# SmartGarden.net
KiCad netlist of a schematic drawn in Altium Designer
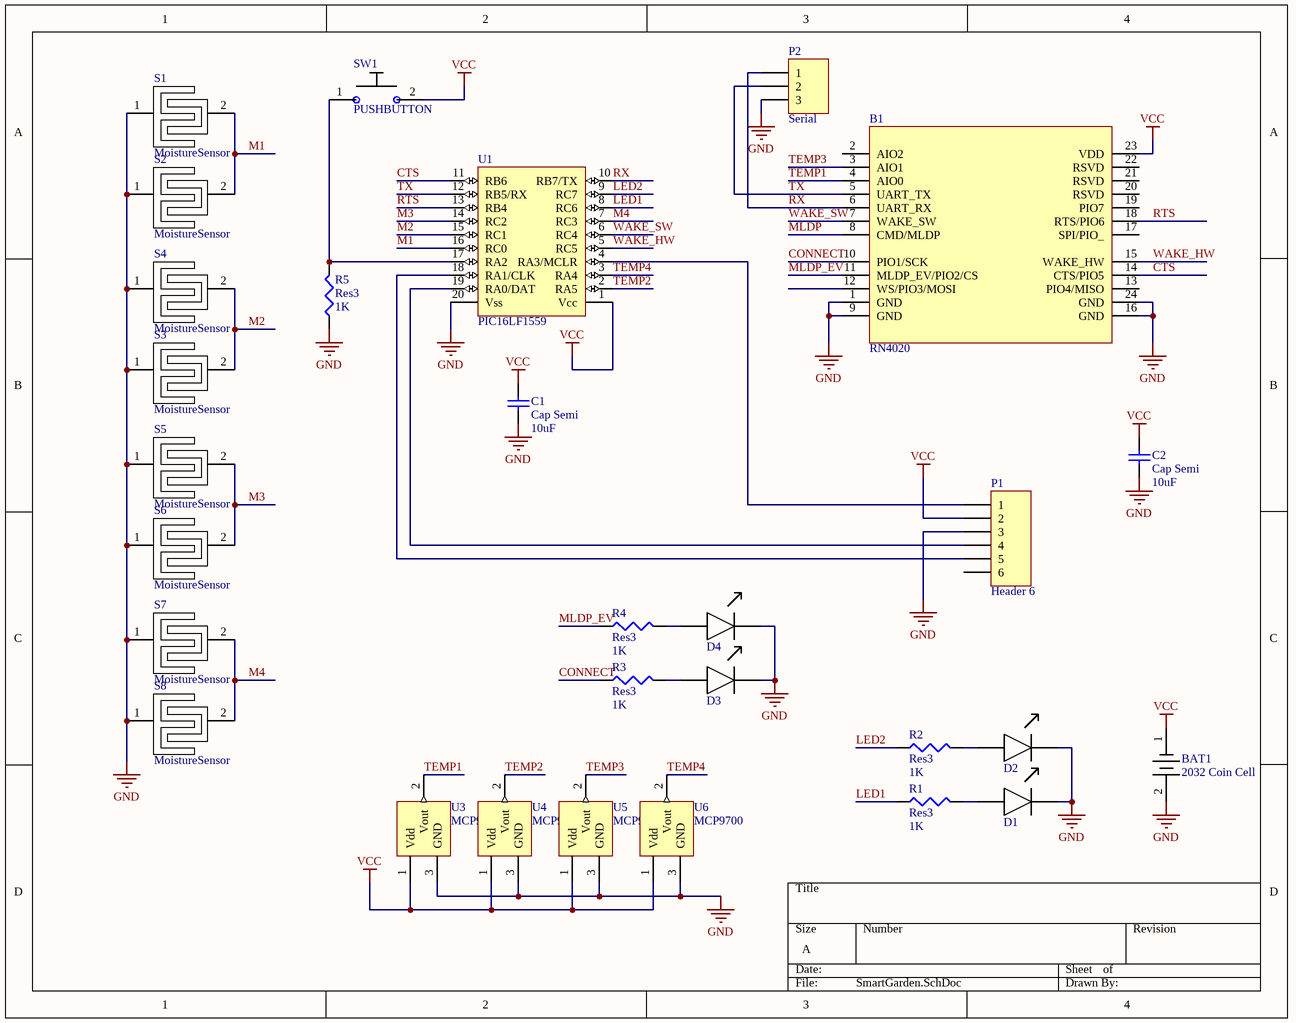
[diagram p0: SmartGarden.SchDoc]

(export (version "E")
  (design (tool "Eeschema 10.0.6"))
  (components
    (comp (ref "B1") (value "RN4020") (footprint "RN4020 MODULE-24") (libsource (lib "Phil") (part "RN4020")))
    (comp (ref "BAT1")
      (value "2032 Coin Cell")
      (footprint "1063TR-CoinCell")
      (libsource (lib "Phil") (part "2032 Coin Cell"))
    )
    (comp (ref "C1")
      (value "Cap Semi")
      (footprint "1608[0603]")
      (description "Capacitor (Semiconductor SIM Model)")
      (fields (field (name "ALTIUM_VALUE") "10uF") (field (name "PUBLISHER") "Altium Limited"))
      (libsource (lib "Miscellaneous Devices") (part "Cap Semi"))
    )
    (comp (ref "C2")
      (value "Cap Semi")
      (footprint "1608[0603]")
      (description "Capacitor (Semiconductor SIM Model)")
      (fields (field (name "ALTIUM_VALUE") "10uF") (field (name "PUBLISHER") "Altium Limited"))
      (libsource (lib "Miscellaneous Devices") (part "Cap Semi"))
    )
    (comp (ref "D1") (value "LED") (footprint "603_") (libsource (lib "Phil") (part "LED")))
    (comp (ref "D2") (value "LED") (footprint "603_") (libsource (lib "Phil") (part "LED")))
    (comp (ref "D3") (value "LED") (footprint "603_") (libsource (lib "Phil") (part "LED")))
    (comp (ref "D4") (value "LED") (footprint "603_") (libsource (lib "Phil") (part "LED")))
    (comp (ref "P1")
      (value "Header 6")
      (footprint "HDR1X6")
      (description "Header, 6-Pin")
      (fields (field (name "PUBLISHER") "Altium Limited"))
      (libsource (lib "Miscellaneous Connectors") (part "Header 6"))
    )
    (comp (ref "P2")
      (value "Serial")
      (footprint "HDR1X3")
      (description "Header, 3-Pin")
      (fields (field (name "PUBLISHER") "Altium Limited"))
      (libsource (lib "Miscellaneous Connectors") (part "Header 3"))
    )
    (comp (ref "R1")
      (value "Res3")
      (footprint "J1-0603")
      (description "Resistor")
      (fields (field (name "ALTIUM_VALUE") "1K") (field (name "PUBLISHER") "Altium Limited"))
      (libsource (lib "Miscellaneous Devices") (part "Res3"))
    )
    (comp (ref "R2")
      (value "Res3")
      (footprint "J1-0603")
      (description "Resistor")
      (fields (field (name "ALTIUM_VALUE") "1K") (field (name "PUBLISHER") "Altium Limited"))
      (libsource (lib "Miscellaneous Devices") (part "Res3"))
    )
    (comp (ref "R3")
      (value "Res3")
      (footprint "J1-0603")
      (description "Resistor")
      (fields (field (name "ALTIUM_VALUE") "1K") (field (name "PUBLISHER") "Altium Limited"))
      (libsource (lib "Miscellaneous Devices") (part "Res3"))
    )
    (comp (ref "R4")
      (value "Res3")
      (footprint "J1-0603")
      (description "Resistor")
      (fields (field (name "ALTIUM_VALUE") "1K") (field (name "PUBLISHER") "Altium Limited"))
      (libsource (lib "Miscellaneous Devices") (part "Res3"))
    )
    (comp (ref "R5")
      (value "Res3")
      (footprint "J1-0603")
      (description "Resistor")
      (fields (field (name "ALTIUM_VALUE") "1K") (field (name "PUBLISHER") "Altium Limited"))
      (libsource (lib "Miscellaneous Devices") (part "Res3"))
    )
    (comp (ref "S1")
      (value "MoistureSensor")
      (footprint "MOISTURE_2")
      (libsource (lib "Phil") (part "MoistureSensor"))
    )
    (comp (ref "S2")
      (value "MoistureSensor")
      (footprint "MOISTURE_2")
      (libsource (lib "Phil") (part "MoistureSensor"))
    )
    (comp (ref "S3")
      (value "MoistureSensor")
      (footprint "MOISTURE_2")
      (libsource (lib "Phil") (part "MoistureSensor"))
    )
    (comp (ref "S4")
      (value "MoistureSensor")
      (footprint "MOISTURE_2")
      (libsource (lib "Phil") (part "MoistureSensor"))
    )
    (comp (ref "S5")
      (value "MoistureSensor")
      (footprint "MOISTURE_2")
      (libsource (lib "Phil") (part "MoistureSensor"))
    )
    (comp (ref "S6")
      (value "MoistureSensor")
      (footprint "MOISTURE_2")
      (libsource (lib "Phil") (part "MoistureSensor"))
    )
    (comp (ref "S7")
      (value "MoistureSensor")
      (footprint "MOISTURE_2")
      (libsource (lib "Phil") (part "MoistureSensor"))
    )
    (comp (ref "S8")
      (value "MoistureSensor")
      (footprint "MOISTURE_2")
      (libsource (lib "Phil") (part "MoistureSensor"))
    )
    (comp (ref "SW1")
      (value "PUSHBUTTON")
      (footprint "PUSHBUTTON")
      (description "TE 5-1437565-0")
      (libsource (lib "Phil") (part "PUSHBUTTON"))
    )
    (comp (ref "U1")
      (value "PIC16LF1559")
      (footprint "SSOP-20")
      (libsource (lib "Phil") (part "PIC16LF1559"))
    )
    (comp (ref "U3")
      (value "MCP9700")
      (footprint "Miscellaneous Devices:SOT23_M")
      (libsource (lib "Phil") (part "MCP9700"))
    )
    (comp (ref "U4")
      (value "MCP9700")
      (footprint "Miscellaneous Devices:SOT23_M")
      (libsource (lib "Phil") (part "MCP9700"))
    )
    (comp (ref "U5")
      (value "MCP9700")
      (footprint "Miscellaneous Devices:SOT23_M")
      (libsource (lib "Phil") (part "MCP9700"))
    )
    (comp (ref "U6")
      (value "MCP9700")
      (footprint "Miscellaneous Devices:SOT23_M")
      (libsource (lib "Phil") (part "MCP9700"))
    )
  )
  (nets
    (net (code "1") (name "/CONNECT") (class "Default")
      (node (ref "B1") (pin "10") (pinfunction "PIO1/SCK_10") (pintype "passive"))
      (node (ref "R3") (pin "1") (pinfunction "1_1") (pintype "passive"))
    )
    (net (code "2") (name "/CTS") (class "Default")
      (node (ref "B1") (pin "14") (pinfunction "CTS/PIO5_14") (pintype "passive"))
      (node (ref "U1") (pin "11") (pinfunction "RB6_11") (pintype "bidirectional"))
    )
    (net (code "3") (name "/LED1") (class "Default")
      (node (ref "R1") (pin "1") (pinfunction "1_1") (pintype "passive"))
      (node (ref "U1") (pin "8") (pinfunction "RC6_8") (pintype "bidirectional"))
    )
    (net (code "4") (name "/LED2") (class "Default")
      (node (ref "R2") (pin "1") (pinfunction "1_1") (pintype "passive"))
      (node (ref "U1") (pin "9") (pinfunction "RC7_9") (pintype "bidirectional"))
    )
    (net (code "5") (name "/M1") (class "Default")
      (node (ref "S1") (pin "2") (pinfunction "2_2") (pintype "passive"))
      (node (ref "S2") (pin "2") (pinfunction "2_2") (pintype "passive"))
      (node (ref "U1") (pin "16") (pinfunction "RC0_16") (pintype "bidirectional"))
    )
    (net (code "6") (name "/M2") (class "Default")
      (node (ref "S3") (pin "2") (pinfunction "2_2") (pintype "passive"))
      (node (ref "S4") (pin "2") (pinfunction "2_2") (pintype "passive"))
      (node (ref "U1") (pin "15") (pinfunction "RC1_15") (pintype "bidirectional"))
    )
    (net (code "7") (name "/M3") (class "Default")
      (node (ref "S5") (pin "2") (pinfunction "2_2") (pintype "passive"))
      (node (ref "S6") (pin "2") (pinfunction "2_2") (pintype "passive"))
      (node (ref "U1") (pin "14") (pinfunction "RC2_14") (pintype "bidirectional"))
    )
    (net (code "8") (name "/M4") (class "Default")
      (node (ref "S7") (pin "2") (pinfunction "2_2") (pintype "passive"))
      (node (ref "S8") (pin "2") (pinfunction "2_2") (pintype "passive"))
      (node (ref "U1") (pin "7") (pinfunction "RC3_7") (pintype "bidirectional"))
    )
    (net (code "9") (name "/MLDP") (class "Default")
      (node (ref "B1") (pin "8") (pinfunction "CMD/MLDP_8") (pintype "passive"))
    )
    (net (code "10") (name "/MLDP_EV") (class "Default")
      (node (ref "B1") (pin "11") (pinfunction "MLDP_EV/PIO2/CS_11") (pintype "passive"))
      (node (ref "R4") (pin "1") (pinfunction "1_1") (pintype "passive"))
    )
    (net (code "11") (name "/RTS") (class "Default")
      (node (ref "B1") (pin "18") (pinfunction "RTS/PIO6_18") (pintype "passive"))
      (node (ref "U1") (pin "13") (pinfunction "RB4_13") (pintype "bidirectional"))
    )
    (net (code "12") (name "/RX") (class "Default")
      (node (ref "B1") (pin "6") (pinfunction "UART_RX_6") (pintype "passive"))
      (node (ref "P2") (pin "1") (pinfunction "1_1") (pintype "passive"))
      (node (ref "U1") (pin "10") (pinfunction "RB7/TX_10") (pintype "bidirectional"))
    )
    (net (code "13") (name "/TEMP1") (class "Default")
      (node (ref "B1") (pin "4") (pinfunction "AIO0_4") (pintype "passive"))
      (node (ref "U3") (pin "2") (pinfunction "Vout_2") (pintype "output"))
    )
    (net (code "14") (name "/TEMP2") (class "Default")
      (node (ref "U1") (pin "2") (pinfunction "RA5_2") (pintype "bidirectional"))
      (node (ref "U4") (pin "2") (pinfunction "Vout_2") (pintype "output"))
    )
    (net (code "15") (name "/TEMP3") (class "Default")
      (node (ref "B1") (pin "3") (pinfunction "AIO1_3") (pintype "passive"))
      (node (ref "U5") (pin "2") (pinfunction "Vout_2") (pintype "output"))
    )
    (net (code "16") (name "/TEMP4") (class "Default")
      (node (ref "U1") (pin "3") (pinfunction "RA4_3") (pintype "bidirectional"))
      (node (ref "U6") (pin "2") (pinfunction "Vout_2") (pintype "output"))
    )
    (net (code "17") (name "/TX") (class "Default")
      (node (ref "B1") (pin "5") (pinfunction "UART_TX_5") (pintype "passive"))
      (node (ref "P2") (pin "2") (pinfunction "2_2") (pintype "passive"))
      (node (ref "U1") (pin "12") (pinfunction "RB5/RX_12") (pintype "bidirectional"))
    )
    (net (code "18") (name "/WAKE_HW") (class "Default")
      (node (ref "B1") (pin "15") (pinfunction "WAKE_HW_15") (pintype "passive"))
      (node (ref "U1") (pin "5") (pinfunction "RC5_5") (pintype "bidirectional"))
    )
    (net (code "19") (name "/WAKE_SW") (class "Default")
      (node (ref "B1") (pin "7") (pinfunction "WAKE_SW_7") (pintype "passive"))
      (node (ref "U1") (pin "6") (pinfunction "RC4_6") (pintype "bidirectional"))
    )
    (net (code "20") (name "GND") (class "Default")
      (node (ref "B1") (pin "1") (pinfunction "GND_1") (pintype "power_in"))
      (node (ref "B1") (pin "16") (pinfunction "GND_16") (pintype "power_in"))
      (node (ref "B1") (pin "24") (pinfunction "GND_24") (pintype "passive"))
      (node (ref "B1") (pin "9") (pinfunction "GND_9") (pintype "power_in"))
      (node (ref "BAT1") (pin "2") (pinfunction "2_2") (pintype "passive"))
      (node (ref "C1") (pin "1") (pinfunction "1_1") (pintype "passive"))
      (node (ref "C2") (pin "1") (pinfunction "1_1") (pintype "passive"))
      (node (ref "D1") (pin "2") (pinfunction "2_2") (pintype "passive"))
      (node (ref "D2") (pin "2") (pinfunction "2_2") (pintype "passive"))
      (node (ref "D3") (pin "2") (pinfunction "2_2") (pintype "passive"))
      (node (ref "D4") (pin "2") (pinfunction "2_2") (pintype "passive"))
      (node (ref "P1") (pin "3") (pinfunction "3_3") (pintype "passive"))
      (node (ref "P2") (pin "3") (pinfunction "3_3") (pintype "passive"))
      (node (ref "R5") (pin "1") (pinfunction "1_1") (pintype "passive"))
      (node (ref "S1") (pin "1") (pinfunction "1_1") (pintype "passive"))
      (node (ref "S2") (pin "1") (pinfunction "1_1") (pintype "passive"))
      (node (ref "S3") (pin "1") (pinfunction "1_1") (pintype "passive"))
      (node (ref "S4") (pin "1") (pinfunction "1_1") (pintype "passive"))
      (node (ref "S5") (pin "1") (pinfunction "1_1") (pintype "passive"))
      (node (ref "S6") (pin "1") (pinfunction "1_1") (pintype "passive"))
      (node (ref "S7") (pin "1") (pinfunction "1_1") (pintype "passive"))
      (node (ref "S8") (pin "1") (pinfunction "1_1") (pintype "passive"))
      (node (ref "U1") (pin "20") (pinfunction "Vss_20") (pintype "power_in"))
      (node (ref "U3") (pin "3") (pinfunction "GND_3") (pintype "power_in"))
      (node (ref "U4") (pin "3") (pinfunction "GND_3") (pintype "power_in"))
      (node (ref "U5") (pin "3") (pinfunction "GND_3") (pintype "power_in"))
      (node (ref "U6") (pin "3") (pinfunction "GND_3") (pintype "power_in"))
    )
    (net (code "21") (name "Net-(D1-Pad1)") (class "Default")
      (node (ref "D1") (pin "1") (pinfunction "1_1") (pintype "passive"))
      (node (ref "R1") (pin "2") (pinfunction "2_2") (pintype "passive"))
    )
    (net (code "22") (name "Net-(D2-Pad1)") (class "Default")
      (node (ref "D2") (pin "1") (pinfunction "1_1") (pintype "passive"))
      (node (ref "R2") (pin "2") (pinfunction "2_2") (pintype "passive"))
    )
    (net (code "23") (name "Net-(D3-Pad1)") (class "Default")
      (node (ref "D3") (pin "1") (pinfunction "1_1") (pintype "passive"))
      (node (ref "R3") (pin "2") (pinfunction "2_2") (pintype "passive"))
    )
    (net (code "24") (name "Net-(D4-Pad1)") (class "Default")
      (node (ref "D4") (pin "1") (pinfunction "1_1") (pintype "passive"))
      (node (ref "R4") (pin "2") (pinfunction "2_2") (pintype "passive"))
    )
    (net (code "25") (name "Net-(U1-RA0{slash}DAT)") (class "Default")
      (node (ref "P1") (pin "4") (pinfunction "4_4") (pintype "passive"))
      (node (ref "U1") (pin "19") (pinfunction "RA0/DAT_19") (pintype "bidirectional"))
    )
    (net (code "26") (name "Net-(U1-RA1{slash}CLK)") (class "Default")
      (node (ref "P1") (pin "5") (pinfunction "5_5") (pintype "passive"))
      (node (ref "U1") (pin "18") (pinfunction "RA1/CLK_18") (pintype "bidirectional"))
    )
    (net (code "27") (name "Net-(U1-RA2)") (class "Default")
      (node (ref "R5") (pin "2") (pinfunction "2_2") (pintype "passive"))
      (node (ref "SW1") (pin "1") (pinfunction "1_1") (pintype "passive"))
      (node (ref "U1") (pin "17") (pinfunction "RA2_17") (pintype "bidirectional"))
    )
    (net (code "28") (name "Net-(U1-RA3{slash}MCLR)") (class "Default")
      (node (ref "P1") (pin "1") (pinfunction "1_1") (pintype "passive"))
      (node (ref "U1") (pin "4") (pinfunction "RA3/MCLR_4") (pintype "bidirectional"))
    )
    (net (code "29") (name "VCC") (class "Default")
      (node (ref "B1") (pin "23") (pinfunction "VDD_23") (pintype "power_in"))
      (node (ref "BAT1") (pin "1") (pinfunction "1_1") (pintype "passive"))
      (node (ref "C1") (pin "2") (pinfunction "2_2") (pintype "passive"))
      (node (ref "C2") (pin "2") (pinfunction "2_2") (pintype "passive"))
      (node (ref "P1") (pin "2") (pinfunction "2_2") (pintype "passive"))
      (node (ref "SW1") (pin "2") (pinfunction "2_2") (pintype "passive"))
      (node (ref "U1") (pin "1") (pinfunction "Vcc_1") (pintype "power_in"))
      (node (ref "U3") (pin "1") (pinfunction "Vdd_1") (pintype "power_in"))
      (node (ref "U4") (pin "1") (pinfunction "Vdd_1") (pintype "power_in"))
      (node (ref "U5") (pin "1") (pinfunction "Vdd_1") (pintype "power_in"))
      (node (ref "U6") (pin "1") (pinfunction "Vdd_1") (pintype "power_in"))
    )
    (net (code "30") (name "unconnected-(B1-AIO2-Pad2)") (class "Default")
      (node (ref "B1") (pin "2") (pinfunction "AIO2_2") (pintype "passive"))
    )
    (net (code "31") (name "unconnected-(B1-PIO4{slash}MISO-Pad13)") (class "Default")
      (node (ref "B1") (pin "13") (pinfunction "PIO4/MISO_13") (pintype "passive"))
    )
    (net (code "32") (name "unconnected-(B1-PIO7-Pad19)") (class "Default")
      (node (ref "B1") (pin "19") (pinfunction "PIO7_19") (pintype "passive"))
    )
    (net (code "33") (name "unconnected-(B1-RSVD-Pad20)") (class "Default")
      (node (ref "B1") (pin "20") (pinfunction "RSVD_20") (pintype "passive"))
    )
    (net (code "34") (name "unconnected-(B1-RSVD-Pad21)") (class "Default")
      (node (ref "B1") (pin "21") (pinfunction "RSVD_21") (pintype "passive"))
    )
    (net (code "35") (name "unconnected-(B1-RSVD-Pad22)") (class "Default")
      (node (ref "B1") (pin "22") (pinfunction "RSVD_22") (pintype "passive"))
    )
    (net (code "36") (name "unconnected-(B1-SPI{slash}PIO_-Pad17)") (class "Default")
      (node (ref "B1") (pin "17") (pinfunction "SPI/PIO__17") (pintype "passive"))
    )
    (net (code "37") (name "unconnected-(B1-WS{slash}PIO3{slash}MOSI-Pad12)") (class "Default")
      (node (ref "B1") (pin "12") (pinfunction "WS/PIO3/MOSI_12") (pintype "passive"))
    )
    (net (code "38") (name "unconnected-(P1-Pad6)") (class "Default")
      (node (ref "P1") (pin "6") (pinfunction "6_6") (pintype "passive"))
    )
  )
)
